# integer_layer.net
KiCad netlist of a schematic drawn in Altium Designer
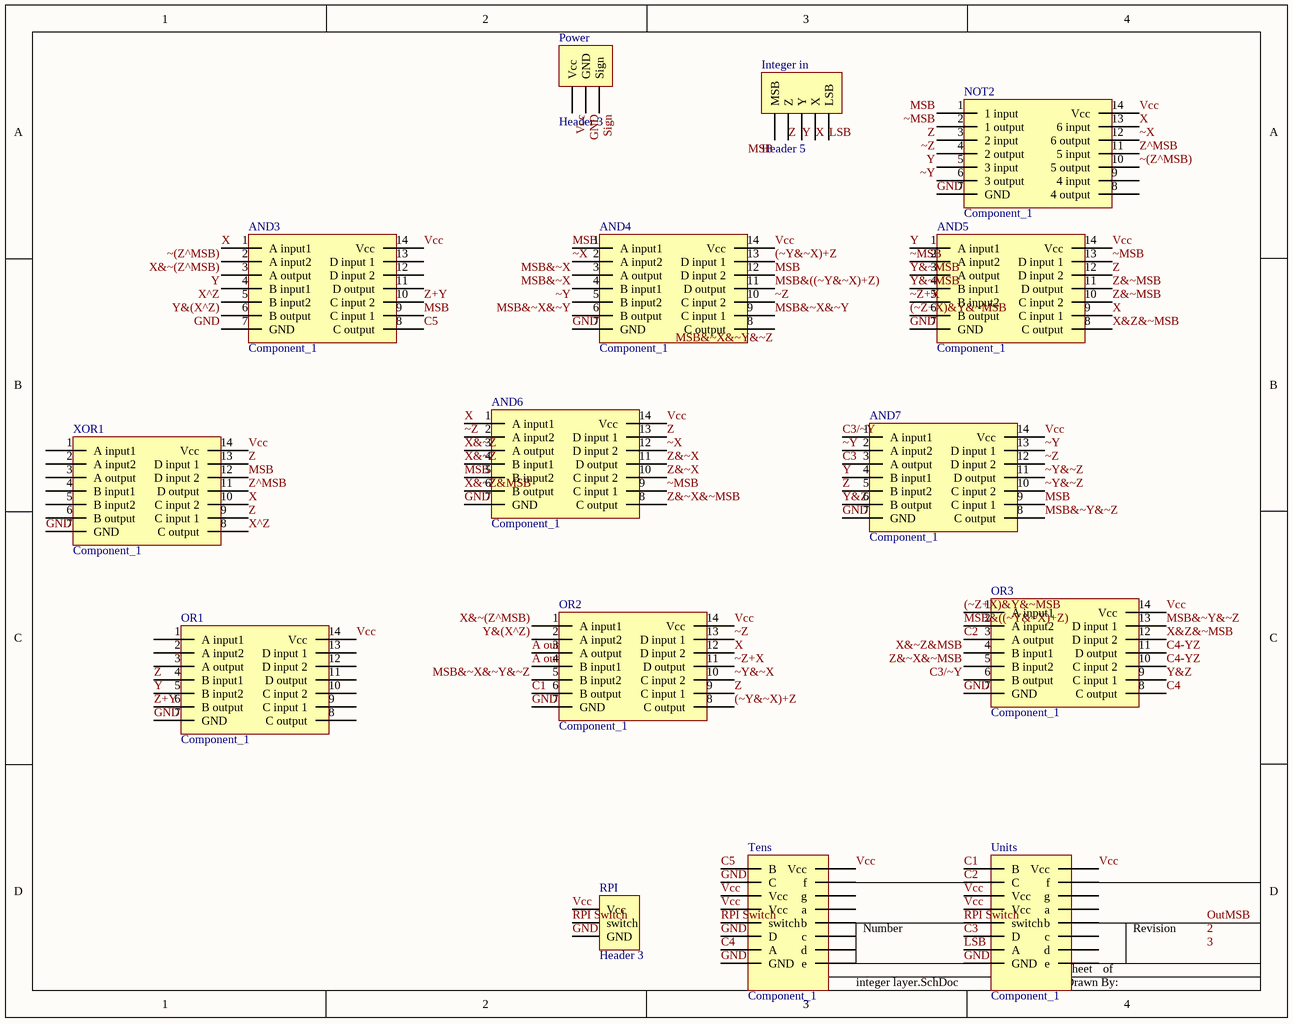
[diagram p0: integer layer.SchDoc]

(export (version "E")
  (design (tool "Eeschema 10.0.6"))
  (components
    (comp (ref "AND3")
      (value "Component_1")
      (footprint "Gate?")
      (libsource (lib "gates library") (part "Component_1"))
    )
    (comp (ref "AND4")
      (value "Component_1")
      (footprint "Gate?")
      (libsource (lib "gates library") (part "Component_1"))
    )
    (comp (ref "AND5")
      (value "Component_1")
      (footprint "Gate?")
      (libsource (lib "gates library") (part "Component_1"))
    )
    (comp (ref "AND6")
      (value "Component_1")
      (footprint "Gate?")
      (libsource (lib "gates library") (part "Component_1"))
    )
    (comp (ref "AND7")
      (value "Component_1")
      (footprint "Gate?")
      (libsource (lib "gates library") (part "Component_1"))
    )
    (comp (ref "Integer in")
      (value "Header 5")
      (footprint "HDR1X5")
      (description "Header, 5-Pin")
      (fields (field (name "PUBLISHER") "Altium Limited"))
      (libsource (lib "Miscellaneous Connectors") (part "Header 5"))
    )
    (comp (ref "NOT2")
      (value "Component_1")
      (footprint "Gate?")
      (libsource (lib "gates library") (part "Component_1"))
    )
    (comp (ref "OR1")
      (value "Component_1")
      (footprint "Gate?")
      (libsource (lib "gates library") (part "Component_1"))
    )
    (comp (ref "OR2")
      (value "Component_1")
      (footprint "Gate?")
      (libsource (lib "gates library") (part "Component_1"))
    )
    (comp (ref "OR3")
      (value "Component_1")
      (footprint "Gate?")
      (libsource (lib "gates library") (part "Component_1"))
    )
    (comp (ref "Power")
      (value "Header 3")
      (footprint "HDR1X3")
      (description "Header, 3-Pin")
      (fields (field (name "PUBLISHER") "Altium Limited"))
      (libsource (lib "Miscellaneous Connectors") (part "Header 3"))
    )
    (comp (ref "RPI")
      (value "Header 3")
      (footprint "HDR1X3")
      (description "Header, 3-Pin")
      (fields (field (name "PUBLISHER") "Altium Limited"))
      (libsource (lib "") (part "Header 3_1"))
    )
    (comp (ref "Tens")
      (value "Component_1")
      (footprint "7483")
      (libsource (lib "4-bit binary adder") (part "Component_1"))
    )
    (comp (ref "Units")
      (value "Component_1")
      (footprint "7483")
      (libsource (lib "4-bit binary adder") (part "Component_1"))
    )
    (comp (ref "XOR1")
      (value "Component_1")
      (footprint "Gate?")
      (libsource (lib "gates library") (part "Component_1"))
    )
  )
  (nets
    (net (code "1") (name "/(~Y&~X)+Z") (class "Default")
      (node (ref "AND4") (pin "13") (pinfunction "D_input_1_13") (pintype "passive"))
      (node (ref "OR2") (pin "8") (pinfunction "C_output_8") (pintype "passive"))
    )
    (net (code "2") (name "/(~Z+X)&Y&~MSB") (class "Default")
      (node (ref "AND5") (pin "6") (pinfunction "B_output_6") (pintype "passive"))
      (node (ref "OR3") (pin "1") (pinfunction "A_input1_1") (pintype "passive"))
    )
    (net (code "5") (name "/A out") (class "Default")
      (node (ref "OR2") (pin "3") (pinfunction "A_output_3") (pintype "passive"))
      (node (ref "OR2") (pin "4") (pinfunction "B_input1_4") (pintype "passive"))
    )
    (net (code "6") (name "/C1") (class "Default")
      (node (ref "OR2") (pin "6") (pinfunction "B_output_6") (pintype "passive"))
      (node (ref "Units") (pin "A4") (pinfunction "B_A4") (pintype "passive"))
    )
    (net (code "7") (name "/C2") (class "Default")
      (node (ref "OR3") (pin "3") (pinfunction "A_output_3") (pintype "passive"))
      (node (ref "Units") (pin "C3") (pinfunction "C_C3") (pintype "passive"))
    )
    (net (code "8") (name "/C3") (class "Default")
      (node (ref "AND7") (pin "3") (pinfunction "A_output_3") (pintype "passive"))
      (node (ref "Units") (pin "C2") (pinfunction "D_C2") (pintype "passive"))
    )
    (net (code "9") (name "/C3{slash}~Y") (class "Default")
      (node (ref "AND7") (pin "1") (pinfunction "A_input1_1") (pintype "passive"))
      (node (ref "OR3") (pin "6") (pinfunction "B_output_6") (pintype "passive"))
    )
    (net (code "10") (name "/C4") (class "Default")
      (node (ref "OR3") (pin "8") (pinfunction "C_output_8") (pintype "passive"))
      (node (ref "Tens") (pin "B2") (pinfunction "A_B2") (pintype "passive"))
    )
    (net (code "11") (name "/C4-YZ") (class "Default")
      (node (ref "OR3") (pin "10") (pinfunction "C_input_2_10") (pintype "passive"))
      (node (ref "OR3") (pin "11") (pinfunction "D_output_11") (pintype "passive"))
    )
    (net (code "12") (name "/C5") (class "Default")
      (node (ref "AND3") (pin "8") (pinfunction "C_output_8") (pintype "passive"))
      (node (ref "Tens") (pin "A4") (pinfunction "B_A4") (pintype "passive"))
    )
    (net (code "13") (name "/GND") (class "Default")
      (node (ref "AND3") (pin "7") (pinfunction "GND_7") (pintype "passive"))
      (node (ref "AND4") (pin "7") (pinfunction "GND_7") (pintype "passive"))
      (node (ref "AND5") (pin "7") (pinfunction "GND_7") (pintype "passive"))
      (node (ref "AND6") (pin "7") (pinfunction "GND_7") (pintype "passive"))
      (node (ref "AND7") (pin "7") (pinfunction "GND_7") (pintype "passive"))
      (node (ref "NOT2") (pin "7") (pinfunction "GND_7") (pintype "passive"))
      (node (ref "OR1") (pin "7") (pinfunction "GND_7") (pintype "passive"))
      (node (ref "OR2") (pin "7") (pinfunction "GND_7") (pintype "passive"))
      (node (ref "OR3") (pin "7") (pinfunction "GND_7") (pintype "passive"))
      (node (ref "Power") (pin "2") (pinfunction "GND_2") (pintype "passive"))
      (node (ref "RPI") (pin "3") (pinfunction "GND_3") (pintype "passive"))
      (node (ref "Tens") (pin "A2") (pinfunction "GND_A2") (pintype "passive"))
      (node (ref "Tens") (pin "C2") (pinfunction "D_C2") (pintype "passive"))
      (node (ref "Tens") (pin "C3") (pinfunction "C_C3") (pintype "passive"))
      (node (ref "Units") (pin "A2") (pinfunction "GND_A2") (pintype "passive"))
      (node (ref "XOR1") (pin "7") (pinfunction "GND_7") (pintype "passive"))
    )
    (net (code "14") (name "/LSB") (class "Default")
      (node (ref "Integer in") (pin "5") (pinfunction "LSB_5") (pintype "passive"))
      (node (ref "Units") (pin "B2") (pinfunction "A_B2") (pintype "passive"))
    )
    (net (code "15") (name "/MSB") (class "Default")
      (node (ref "AND3") (pin "9") (pinfunction "C_input_1_9") (pintype "passive"))
      (node (ref "AND4") (pin "1") (pinfunction "A_input1_1") (pintype "passive"))
      (node (ref "AND4") (pin "12") (pinfunction "D_input_2_12") (pintype "passive"))
      (node (ref "AND6") (pin "5") (pinfunction "B_input2_5") (pintype "passive"))
      (node (ref "AND7") (pin "9") (pinfunction "C_input_1_9") (pintype "passive"))
      (node (ref "Integer in") (pin "1") (pinfunction "MSB_1") (pintype "passive"))
      (node (ref "NOT2") (pin "1") (pinfunction "A_input1_1") (pintype "passive"))
      (node (ref "XOR1") (pin "12") (pinfunction "D_input_2_12") (pintype "passive"))
    )
    (net (code "16") (name "/MSB&((~Y&~X)+Z)") (class "Default")
      (node (ref "AND4") (pin "11") (pinfunction "D_output_11") (pintype "passive"))
      (node (ref "OR3") (pin "2") (pinfunction "A_input2_2") (pintype "passive"))
    )
    (net (code "17") (name "/MSB&~X") (class "Default")
      (node (ref "AND4") (pin "3") (pinfunction "A_output_3") (pintype "passive"))
      (node (ref "AND4") (pin "4") (pinfunction "B_input1_4") (pintype "passive"))
    )
    (net (code "18") (name "/MSB&~X&~Y") (class "Default")
      (node (ref "AND4") (pin "6") (pinfunction "B_output_6") (pintype "passive"))
      (node (ref "AND4") (pin "9") (pinfunction "C_input_1_9") (pintype "passive"))
    )
    (net (code "19") (name "/MSB&~X&~Y&~Z") (class "Default")
      (node (ref "AND4") (pin "8") (pinfunction "C_output_8") (pintype "passive"))
      (node (ref "OR2") (pin "5") (pinfunction "B_input2_5") (pintype "passive"))
    )
    (net (code "20") (name "/MSB&~Y&~Z") (class "Default")
      (node (ref "AND7") (pin "8") (pinfunction "C_output_8") (pintype "passive"))
      (node (ref "OR3") (pin "13") (pinfunction "D_input_1_13") (pintype "passive"))
    )
    (net (code "22") (name "/RPI Switch") (class "Default")
      (node (ref "RPI") (pin "2") (pinfunction "switch_2") (pintype "passive"))
      (node (ref "Tens") (pin "Vcc") (pinfunction "switch_Vcc") (pintype "passive"))
      (node (ref "Units") (pin "Vcc") (pinfunction "switch_Vcc") (pintype "passive"))
    )
    (net (code "23") (name "/Sign") (class "Default")
      (node (ref "Power") (pin "3") (pinfunction "Sign_3") (pintype "passive"))
    )
    (net (code "24") (name "/Vcc") (class "Default")
      (node (ref "AND3") (pin "14") (pinfunction "Vcc_14") (pintype "passive"))
      (node (ref "AND4") (pin "14") (pinfunction "Vcc_14") (pintype "passive"))
      (node (ref "AND5") (pin "14") (pinfunction "Vcc_14") (pintype "passive"))
      (node (ref "AND6") (pin "14") (pinfunction "Vcc_14") (pintype "passive"))
      (node (ref "AND7") (pin "14") (pinfunction "Vcc_14") (pintype "passive"))
      (node (ref "NOT2") (pin "14") (pinfunction "Vcc_14") (pintype "passive"))
      (node (ref "OR1") (pin "14") (pinfunction "Vcc_14") (pintype "passive"))
      (node (ref "OR2") (pin "14") (pinfunction "Vcc_14") (pintype "passive"))
      (node (ref "OR3") (pin "14") (pinfunction "Vcc_14") (pintype "passive"))
      (node (ref "Power") (pin "1") (pinfunction "Vcc_1") (pintype "passive"))
      (node (ref "RPI") (pin "1") (pinfunction "Vcc_1") (pintype "passive"))
      (node (ref "Tens") (pin "A3") (pinfunction "Vcc_A3") (pintype "passive"))
      (node (ref "Tens") (pin "B3") (pinfunction "Vcc_B3") (pintype "passive"))
      (node (ref "Tens") (pin "B4") (pinfunction "Vcc_B4") (pintype "passive"))
      (node (ref "Units") (pin "A3") (pinfunction "Vcc_A3") (pintype "passive"))
      (node (ref "Units") (pin "B3") (pinfunction "Vcc_B3") (pintype "passive"))
      (node (ref "Units") (pin "B4") (pinfunction "Vcc_B4") (pintype "passive"))
      (node (ref "XOR1") (pin "14") (pinfunction "Vcc_14") (pintype "passive"))
    )
    (net (code "25") (name "/X") (class "Default")
      (node (ref "AND3") (pin "1") (pinfunction "A_input1_1") (pintype "passive"))
      (node (ref "AND5") (pin "9") (pinfunction "C_input_1_9") (pintype "passive"))
      (node (ref "AND6") (pin "1") (pinfunction "A_input1_1") (pintype "passive"))
      (node (ref "Integer in") (pin "4") (pinfunction "X_4") (pintype "passive"))
      (node (ref "NOT2") (pin "13") (pinfunction "D_input_1_13") (pintype "passive"))
      (node (ref "OR2") (pin "12") (pinfunction "D_input_2_12") (pintype "passive"))
      (node (ref "XOR1") (pin "10") (pinfunction "C_input_2_10") (pintype "passive"))
    )
    (net (code "26") (name "/X&Z&~MSB") (class "Default")
      (node (ref "AND5") (pin "8") (pinfunction "C_output_8") (pintype "passive"))
      (node (ref "OR3") (pin "12") (pinfunction "D_input_2_12") (pintype "passive"))
    )
    (net (code "27") (name "/X&~(Z^MSB)") (class "Default")
      (node (ref "AND3") (pin "3") (pinfunction "A_output_3") (pintype "passive"))
      (node (ref "OR2") (pin "1") (pinfunction "A_input1_1") (pintype "passive"))
    )
    (net (code "28") (name "/X&~Z") (class "Default")
      (node (ref "AND6") (pin "3") (pinfunction "A_output_3") (pintype "passive"))
      (node (ref "AND6") (pin "4") (pinfunction "B_input1_4") (pintype "passive"))
    )
    (net (code "29") (name "/X&~Z&MSB") (class "Default")
      (node (ref "AND6") (pin "6") (pinfunction "B_output_6") (pintype "passive"))
      (node (ref "OR3") (pin "4") (pinfunction "B_input1_4") (pintype "passive"))
    )
    (net (code "30") (name "/X^Z") (class "Default")
      (node (ref "AND3") (pin "5") (pinfunction "B_input2_5") (pintype "passive"))
      (node (ref "XOR1") (pin "8") (pinfunction "C_output_8") (pintype "passive"))
    )
    (net (code "31") (name "/Y") (class "Default")
      (node (ref "AND3") (pin "4") (pinfunction "B_input1_4") (pintype "passive"))
      (node (ref "AND5") (pin "1") (pinfunction "A_input1_1") (pintype "passive"))
      (node (ref "AND7") (pin "4") (pinfunction "B_input1_4") (pintype "passive"))
      (node (ref "Integer in") (pin "3") (pinfunction "Y_3") (pintype "passive"))
      (node (ref "NOT2") (pin "5") (pinfunction "B_input2_5") (pintype "passive"))
      (node (ref "OR1") (pin "5") (pinfunction "B_input2_5") (pintype "passive"))
    )
    (net (code "32") (name "/Y&(X^Z)") (class "Default")
      (node (ref "AND3") (pin "6") (pinfunction "B_output_6") (pintype "passive"))
      (node (ref "OR2") (pin "2") (pinfunction "A_input2_2") (pintype "passive"))
    )
    (net (code "33") (name "/Y&Z") (class "Default")
      (node (ref "AND7") (pin "6") (pinfunction "B_output_6") (pintype "passive"))
      (node (ref "OR3") (pin "9") (pinfunction "C_input_1_9") (pintype "passive"))
    )
    (net (code "34") (name "/Y&~MSB") (class "Default")
      (node (ref "AND5") (pin "3") (pinfunction "A_output_3") (pintype "passive"))
      (node (ref "AND5") (pin "4") (pinfunction "B_input1_4") (pintype "passive"))
    )
    (net (code "35") (name "/Z") (class "Default")
      (node (ref "AND5") (pin "12") (pinfunction "D_input_2_12") (pintype "passive"))
      (node (ref "AND6") (pin "13") (pinfunction "D_input_1_13") (pintype "passive"))
      (node (ref "AND7") (pin "5") (pinfunction "B_input2_5") (pintype "passive"))
      (node (ref "Integer in") (pin "2") (pinfunction "Z_2") (pintype "passive"))
      (node (ref "NOT2") (pin "3") (pinfunction "A_output_3") (pintype "passive"))
      (node (ref "OR1") (pin "4") (pinfunction "B_input1_4") (pintype "passive"))
      (node (ref "OR2") (pin "9") (pinfunction "C_input_1_9") (pintype "passive"))
      (node (ref "XOR1") (pin "13") (pinfunction "D_input_1_13") (pintype "passive"))
      (node (ref "XOR1") (pin "9") (pinfunction "C_input_1_9") (pintype "passive"))
    )
    (net (code "36") (name "/Z&~MSB") (class "Default")
      (node (ref "AND5") (pin "10") (pinfunction "C_input_2_10") (pintype "passive"))
      (node (ref "AND5") (pin "11") (pinfunction "D_output_11") (pintype "passive"))
    )
    (net (code "37") (name "/Z&~X") (class "Default")
      (node (ref "AND6") (pin "10") (pinfunction "C_input_2_10") (pintype "passive"))
      (node (ref "AND6") (pin "11") (pinfunction "D_output_11") (pintype "passive"))
    )
    (net (code "38") (name "/Z&~X&~MSB") (class "Default")
      (node (ref "AND6") (pin "8") (pinfunction "C_output_8") (pintype "passive"))
      (node (ref "OR3") (pin "5") (pinfunction "B_input2_5") (pintype "passive"))
    )
    (net (code "39") (name "/Z+Y") (class "Default")
      (node (ref "AND3") (pin "10") (pinfunction "C_input_2_10") (pintype "passive"))
      (node (ref "OR1") (pin "6") (pinfunction "B_output_6") (pintype "passive"))
    )
    (net (code "40") (name "/Z^MSB") (class "Default")
      (node (ref "NOT2") (pin "11") (pinfunction "D_output_11") (pintype "passive"))
      (node (ref "XOR1") (pin "11") (pinfunction "D_output_11") (pintype "passive"))
    )
    (net (code "41") (name "/~(Z^MSB)") (class "Default")
      (node (ref "AND3") (pin "2") (pinfunction "A_input2_2") (pintype "passive"))
      (node (ref "NOT2") (pin "10") (pinfunction "C_input_2_10") (pintype "passive"))
    )
    (net (code "42") (name "/~MSB") (class "Default")
      (node (ref "AND5") (pin "13") (pinfunction "D_input_1_13") (pintype "passive"))
      (node (ref "AND5") (pin "2") (pinfunction "A_input2_2") (pintype "passive"))
      (node (ref "AND6") (pin "9") (pinfunction "C_input_1_9") (pintype "passive"))
      (node (ref "NOT2") (pin "2") (pinfunction "A_input2_2") (pintype "passive"))
    )
    (net (code "43") (name "/~X") (class "Default")
      (node (ref "AND4") (pin "2") (pinfunction "A_input2_2") (pintype "passive"))
      (node (ref "AND6") (pin "12") (pinfunction "D_input_2_12") (pintype "passive"))
      (node (ref "NOT2") (pin "12") (pinfunction "D_input_2_12") (pintype "passive"))
    )
    (net (code "44") (name "/~Y") (class "Default")
      (node (ref "AND4") (pin "5") (pinfunction "B_input2_5") (pintype "passive"))
      (node (ref "AND7") (pin "13") (pinfunction "D_input_1_13") (pintype "passive"))
      (node (ref "AND7") (pin "2") (pinfunction "A_input2_2") (pintype "passive"))
      (node (ref "NOT2") (pin "6") (pinfunction "B_output_6") (pintype "passive"))
    )
    (net (code "45") (name "/~Y&~X") (class "Default")
      (node (ref "OR2") (pin "10") (pinfunction "C_input_2_10") (pintype "passive"))
    )
    (net (code "46") (name "/~Y&~Z") (class "Default")
      (node (ref "AND7") (pin "10") (pinfunction "C_input_2_10") (pintype "passive"))
      (node (ref "AND7") (pin "11") (pinfunction "D_output_11") (pintype "passive"))
    )
    (net (code "47") (name "/~Z") (class "Default")
      (node (ref "AND4") (pin "10") (pinfunction "C_input_2_10") (pintype "passive"))
      (node (ref "AND6") (pin "2") (pinfunction "A_input2_2") (pintype "passive"))
      (node (ref "AND7") (pin "12") (pinfunction "D_input_2_12") (pintype "passive"))
      (node (ref "NOT2") (pin "4") (pinfunction "B_input1_4") (pintype "passive"))
      (node (ref "OR2") (pin "13") (pinfunction "D_input_1_13") (pintype "passive"))
    )
    (net (code "48") (name "/~Z+X") (class "Default")
      (node (ref "AND5") (pin "5") (pinfunction "B_input2_5") (pintype "passive"))
      (node (ref "OR2") (pin "11") (pinfunction "D_output_11") (pintype "passive"))
    )
    (net (code "49") (name "unconnected-(AND3-D_input_1-Pad13)") (class "Default")
      (node (ref "AND3") (pin "13") (pinfunction "D_input_1_13") (pintype "passive"))
    )
    (net (code "50") (name "unconnected-(AND3-D_input_2-Pad12)") (class "Default")
      (node (ref "AND3") (pin "12") (pinfunction "D_input_2_12") (pintype "passive"))
    )
    (net (code "51") (name "unconnected-(AND3-D_output-Pad11)") (class "Default")
      (node (ref "AND3") (pin "11") (pinfunction "D_output_11") (pintype "passive"))
    )
    (net (code "52") (name "unconnected-(NOT2-C_input_1-Pad9)") (class "Default")
      (node (ref "NOT2") (pin "9") (pinfunction "C_input_1_9") (pintype "passive"))
    )
    (net (code "53") (name "unconnected-(NOT2-C_output-Pad8)") (class "Default")
      (node (ref "NOT2") (pin "8") (pinfunction "C_output_8") (pintype "passive"))
    )
    (net (code "54") (name "unconnected-(OR1-A_input1-Pad1)") (class "Default")
      (node (ref "OR1") (pin "1") (pinfunction "A_input1_1") (pintype "passive"))
    )
    (net (code "55") (name "unconnected-(OR1-A_input2-Pad2)") (class "Default")
      (node (ref "OR1") (pin "2") (pinfunction "A_input2_2") (pintype "passive"))
    )
    (net (code "56") (name "unconnected-(OR1-A_output-Pad3)") (class "Default")
      (node (ref "OR1") (pin "3") (pinfunction "A_output_3") (pintype "passive"))
    )
    (net (code "57") (name "unconnected-(OR1-C_input_1-Pad9)") (class "Default")
      (node (ref "OR1") (pin "9") (pinfunction "C_input_1_9") (pintype "passive"))
    )
    (net (code "58") (name "unconnected-(OR1-C_input_2-Pad10)") (class "Default")
      (node (ref "OR1") (pin "10") (pinfunction "C_input_2_10") (pintype "passive"))
    )
    (net (code "59") (name "unconnected-(OR1-C_output-Pad8)") (class "Default")
      (node (ref "OR1") (pin "8") (pinfunction "C_output_8") (pintype "passive"))
    )
    (net (code "60") (name "unconnected-(OR1-D_input_1-Pad13)") (class "Default")
      (node (ref "OR1") (pin "13") (pinfunction "D_input_1_13") (pintype "passive"))
    )
    (net (code "61") (name "unconnected-(OR1-D_input_2-Pad12)") (class "Default")
      (node (ref "OR1") (pin "12") (pinfunction "D_input_2_12") (pintype "passive"))
    )
    (net (code "62") (name "unconnected-(OR1-D_output-Pad11)") (class "Default")
      (node (ref "OR1") (pin "11") (pinfunction "D_output_11") (pintype "passive"))
    )
    (net (code "63") (name "unconnected-(Tens-a-PadC0)") (class "Default")
      (node (ref "Tens") (pin "C0") (pinfunction "a_C0") (pintype "passive"))
    )
    (net (code "64") (name "unconnected-(Tens-b-PadGND)") (class "Default")
      (node (ref "Tens") (pin "GND") (pinfunction "b_GND") (pintype "passive"))
    )
    (net (code "65") (name "unconnected-(Tens-c-PadB1)") (class "Default")
      (node (ref "Tens") (pin "B1") (pinfunction "c_B1") (pintype "passive"))
    )
    (net (code "66") (name "unconnected-(Tens-d-PadA1)") (class "Default")
      (node (ref "Tens") (pin "A1") (pinfunction "d_A1") (pintype "passive"))
    )
    (net (code "67") (name "unconnected-(Tens-e-PadC1)") (class "Default")
      (node (ref "Tens") (pin "C1") (pinfunction "e_C1") (pintype "passive"))
    )
    (net (code "68") (name "unconnected-(Tens-f-PadC4)") (class "Default")
      (node (ref "Tens") (pin "C4") (pinfunction "f_C4") (pintype "passive"))
    )
    (net (code "69") (name "unconnected-(Tens-g-PadC5)") (class "Default")
      (node (ref "Tens") (pin "C5") (pinfunction "g_C5") (pintype "passive"))
    )
    (net (code "70") (name "unconnected-(Units-a-PadC0)") (class "Default")
      (node (ref "Units") (pin "C0") (pinfunction "a_C0") (pintype "passive"))
    )
    (net (code "71") (name "unconnected-(Units-b-PadGND)") (class "Default")
      (node (ref "Units") (pin "GND") (pinfunction "b_GND") (pintype "passive"))
    )
    (net (code "72") (name "unconnected-(Units-c-PadB1)") (class "Default")
      (node (ref "Units") (pin "B1") (pinfunction "c_B1") (pintype "passive"))
    )
    (net (code "73") (name "unconnected-(Units-d-PadA1)") (class "Default")
      (node (ref "Units") (pin "A1") (pinfunction "d_A1") (pintype "passive"))
    )
    (net (code "74") (name "unconnected-(Units-e-PadC1)") (class "Default")
      (node (ref "Units") (pin "C1") (pinfunction "e_C1") (pintype "passive"))
    )
    (net (code "75") (name "unconnected-(Units-f-PadC4)") (class "Default")
      (node (ref "Units") (pin "C4") (pinfunction "f_C4") (pintype "passive"))
    )
    (net (code "76") (name "unconnected-(Units-g-PadC5)") (class "Default")
      (node (ref "Units") (pin "C5") (pinfunction "g_C5") (pintype "passive"))
    )
    (net (code "77") (name "unconnected-(XOR1-A_input1-Pad1)") (class "Default")
      (node (ref "XOR1") (pin "1") (pinfunction "A_input1_1") (pintype "passive"))
    )
    (net (code "78") (name "unconnected-(XOR1-A_input2-Pad2)") (class "Default")
      (node (ref "XOR1") (pin "2") (pinfunction "A_input2_2") (pintype "passive"))
    )
    (net (code "79") (name "unconnected-(XOR1-A_output-Pad3)") (class "Default")
      (node (ref "XOR1") (pin "3") (pinfunction "A_output_3") (pintype "passive"))
    )
    (net (code "80") (name "unconnected-(XOR1-B_input1-Pad4)") (class "Default")
      (node (ref "XOR1") (pin "4") (pinfunction "B_input1_4") (pintype "passive"))
    )
    (net (code "81") (name "unconnected-(XOR1-B_input2-Pad5)") (class "Default")
      (node (ref "XOR1") (pin "5") (pinfunction "B_input2_5") (pintype "passive"))
    )
    (net (code "82") (name "unconnected-(XOR1-B_output-Pad6)") (class "Default")
      (node (ref "XOR1") (pin "6") (pinfunction "B_output_6") (pintype "passive"))
    )
  )
)
